# ethernet_chip.net
KiCad netlist of a schematic drawn in EAGLE
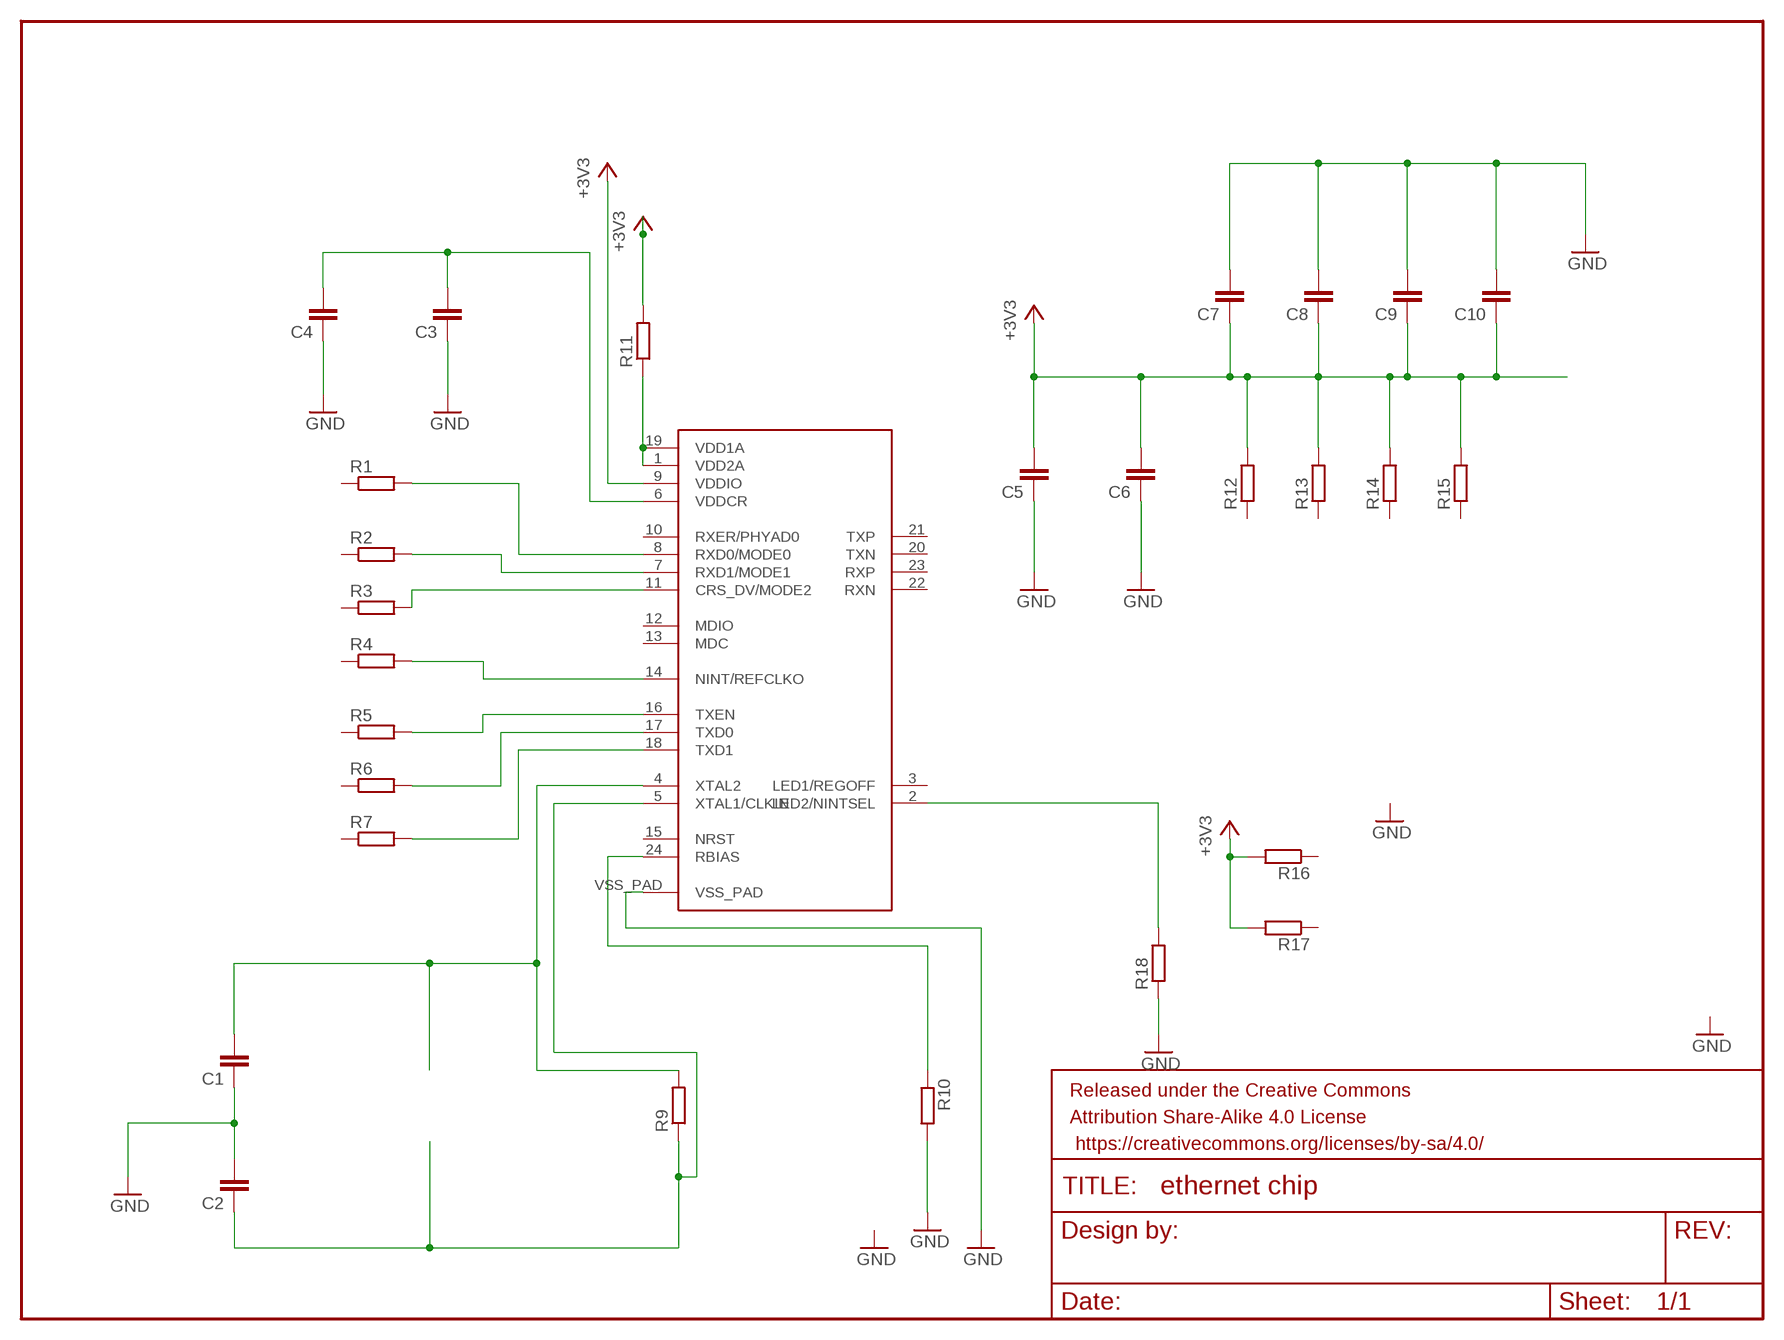
[diagram p0: schematic, sheet 1]

(export (version "E")
  (design (tool "Eeschema 10.0.6"))
  (components
    (comp (ref "C1")
      (value "CC0603")
      (footprint "eagle-import:C0603")
      (libsource (lib "eagle-import") (part "CC0603"))
    )
    (comp (ref "C2")
      (value "CC0603")
      (footprint "eagle-import:C0603")
      (libsource (lib "eagle-import") (part "CC0603"))
    )
    (comp (ref "C3")
      (value "CC0603")
      (footprint "eagle-import:C0603")
      (libsource (lib "eagle-import") (part "CC0603"))
    )
    (comp (ref "C4")
      (value "CC0603")
      (footprint "eagle-import:C0603")
      (libsource (lib "eagle-import") (part "CC0603"))
    )
    (comp (ref "C5")
      (value "CC0603")
      (footprint "eagle-import:C0603")
      (libsource (lib "eagle-import") (part "CC0603"))
    )
    (comp (ref "C6")
      (value "CC0603")
      (footprint "eagle-import:C0603")
      (libsource (lib "eagle-import") (part "CC0603"))
    )
    (comp (ref "C7")
      (value "CC0603")
      (footprint "eagle-import:C0603")
      (libsource (lib "eagle-import") (part "CC0603"))
    )
    (comp (ref "C8")
      (value "CC0603")
      (footprint "eagle-import:C0603")
      (libsource (lib "eagle-import") (part "CC0603"))
    )
    (comp (ref "C9")
      (value "CC0603")
      (footprint "eagle-import:C0603")
      (libsource (lib "eagle-import") (part "CC0603"))
    )
    (comp (ref "C10")
      (value "CC0603")
      (footprint "eagle-import:C0603")
      (libsource (lib "eagle-import") (part "CC0603"))
    )
    (comp (ref "FRAME1")
      (value "FRAME-LETTER")
      (footprint "eagle-import:CREATIVE_COMMONS")
      (libsource (lib "eagle-import") (part "FRAME-LETTER"))
    )
    (comp (ref "R1")
      (value "RR0603")
      (footprint "eagle-import:R0603")
      (libsource (lib "eagle-import") (part "RR0603"))
    )
    (comp (ref "R2")
      (value "RR0603")
      (footprint "eagle-import:R0603")
      (libsource (lib "eagle-import") (part "RR0603"))
    )
    (comp (ref "R3")
      (value "RR0603")
      (footprint "eagle-import:R0603")
      (libsource (lib "eagle-import") (part "RR0603"))
    )
    (comp (ref "R4")
      (value "RR0603")
      (footprint "eagle-import:R0603")
      (libsource (lib "eagle-import") (part "RR0603"))
    )
    (comp (ref "R5")
      (value "RR0603")
      (footprint "eagle-import:R0603")
      (libsource (lib "eagle-import") (part "RR0603"))
    )
    (comp (ref "R6")
      (value "RR0603")
      (footprint "eagle-import:R0603")
      (libsource (lib "eagle-import") (part "RR0603"))
    )
    (comp (ref "R7")
      (value "RR0603")
      (footprint "eagle-import:R0603")
      (libsource (lib "eagle-import") (part "RR0603"))
    )
    (comp (ref "R9")
      (value "RR0603")
      (footprint "eagle-import:R0603")
      (libsource (lib "eagle-import") (part "RR0603"))
    )
    (comp (ref "R10")
      (value "RR0603")
      (footprint "eagle-import:R0603")
      (libsource (lib "eagle-import") (part "RR0603"))
    )
    (comp (ref "R11")
      (value "RR0603")
      (footprint "eagle-import:R0603")
      (libsource (lib "eagle-import") (part "RR0603"))
    )
    (comp (ref "R12")
      (value "RR0603")
      (footprint "eagle-import:R0603")
      (libsource (lib "eagle-import") (part "RR0603"))
    )
    (comp (ref "R13")
      (value "RR0603")
      (footprint "eagle-import:R0603")
      (libsource (lib "eagle-import") (part "RR0603"))
    )
    (comp (ref "R14")
      (value "RR0603")
      (footprint "eagle-import:R0603")
      (libsource (lib "eagle-import") (part "RR0603"))
    )
    (comp (ref "R15")
      (value "RR0603")
      (footprint "eagle-import:R0603")
      (libsource (lib "eagle-import") (part "RR0603"))
    )
    (comp (ref "R16")
      (value "RR0603")
      (footprint "eagle-import:R0603")
      (libsource (lib "eagle-import") (part "RR0603"))
    )
    (comp (ref "R17")
      (value "RR0603")
      (footprint "eagle-import:R0603")
      (libsource (lib "eagle-import") (part "RR0603"))
    )
    (comp (ref "R18")
      (value "RR0603")
      (footprint "eagle-import:R0603")
      (libsource (lib "eagle-import") (part "RR0603"))
    )
    (comp (ref "U$1")
      (value "LAN8720LAN8720")
      (footprint "eagle-import:24-QFN")
      (libsource (lib "eagle-import") (part "LAN8720LAN8720"))
    )
  )
  (nets
    (net (code "1") (name "+3V3") (class "Default")
      (node (ref "C10") (pin "1") (pinfunction "1_1") (pintype "passive"))
      (node (ref "C5") (pin "2") (pinfunction "2_2") (pintype "passive"))
      (node (ref "C6") (pin "2") (pinfunction "2_2") (pintype "passive"))
      (node (ref "C7") (pin "1") (pinfunction "1_1") (pintype "passive"))
      (node (ref "C8") (pin "1") (pinfunction "1_1") (pintype "passive"))
      (node (ref "C9") (pin "1") (pinfunction "1_1") (pintype "passive"))
      (node (ref "R11") (pin "2") (pinfunction "2_2") (pintype "passive"))
      (node (ref "R12") (pin "2") (pinfunction "2_2") (pintype "passive"))
      (node (ref "R13") (pin "2") (pinfunction "2_2") (pintype "passive"))
      (node (ref "R14") (pin "2") (pinfunction "2_2") (pintype "passive"))
      (node (ref "R15") (pin "2") (pinfunction "2_2") (pintype "passive"))
      (node (ref "R16") (pin "2") (pinfunction "2_2") (pintype "passive"))
      (node (ref "R17") (pin "2") (pinfunction "2_2") (pintype "passive"))
      (node (ref "U$1") (pin "9") (pinfunction "VDDIO_9") (pintype "bidirectional"))
    )
    (net (code "2") (name "GND") (class "Default")
      (node (ref "C1") (pin "1") (pinfunction "1_1") (pintype "passive"))
      (node (ref "C10") (pin "2") (pinfunction "2_2") (pintype "passive"))
      (node (ref "C2") (pin "2") (pinfunction "2_2") (pintype "passive"))
      (node (ref "C3") (pin "1") (pinfunction "1_1") (pintype "passive"))
      (node (ref "C4") (pin "1") (pinfunction "1_1") (pintype "passive"))
      (node (ref "C5") (pin "1") (pinfunction "1_1") (pintype "passive"))
      (node (ref "C6") (pin "1") (pinfunction "1_1") (pintype "passive"))
      (node (ref "C7") (pin "2") (pinfunction "2_2") (pintype "passive"))
      (node (ref "C8") (pin "2") (pinfunction "2_2") (pintype "passive"))
      (node (ref "C9") (pin "2") (pinfunction "2_2") (pintype "passive"))
      (node (ref "R10") (pin "2") (pinfunction "2_2") (pintype "passive"))
      (node (ref "R18") (pin "1") (pinfunction "1_1") (pintype "passive"))
      (node (ref "U$1") (pin "VSS_PAD") (pinfunction "VSS_PAD_VSS_PAD") (pintype "bidirectional"))
    )
    (net (code "3") (name "Net-(U$1-CRS_DV{slash}MODE2)") (class "Default")
      (node (ref "R3") (pin "2") (pinfunction "2_2") (pintype "passive"))
      (node (ref "U$1") (pin "11") (pinfunction "CRS_DV/MODE2_11") (pintype "bidirectional"))
    )
    (net (code "4") (name "Net-(U$1-LED2{slash}NINTSEL)") (class "Default")
      (node (ref "R18") (pin "2") (pinfunction "2_2") (pintype "passive"))
      (node (ref "U$1") (pin "2") (pinfunction "LED2/NINTSEL_2") (pintype "bidirectional"))
    )
    (net (code "5") (name "Net-(U$1-NINT{slash}REFCLKO)") (class "Default")
      (node (ref "R4") (pin "2") (pinfunction "2_2") (pintype "passive"))
      (node (ref "U$1") (pin "14") (pinfunction "NINT/REFCLKO_14") (pintype "bidirectional"))
    )
    (net (code "6") (name "Net-(U$1-RBIAS)") (class "Default")
      (node (ref "R10") (pin "1") (pinfunction "1_1") (pintype "passive"))
      (node (ref "U$1") (pin "24") (pinfunction "RBIAS_24") (pintype "bidirectional"))
    )
    (net (code "7") (name "Net-(U$1-RXD0{slash}MODE0)") (class "Default")
      (node (ref "R1") (pin "2") (pinfunction "2_2") (pintype "passive"))
      (node (ref "U$1") (pin "8") (pinfunction "RXD0/MODE0_8") (pintype "bidirectional"))
    )
    (net (code "8") (name "Net-(U$1-RXD1{slash}MODE1)") (class "Default")
      (node (ref "R2") (pin "2") (pinfunction "2_2") (pintype "passive"))
      (node (ref "U$1") (pin "7") (pinfunction "RXD1/MODE1_7") (pintype "bidirectional"))
    )
    (net (code "9") (name "Net-(U$1-TXD0)") (class "Default")
      (node (ref "R6") (pin "2") (pinfunction "2_2") (pintype "passive"))
      (node (ref "U$1") (pin "17") (pinfunction "TXD0_17") (pintype "bidirectional"))
    )
    (net (code "10") (name "Net-(U$1-TXD1)") (class "Default")
      (node (ref "R7") (pin "2") (pinfunction "2_2") (pintype "passive"))
      (node (ref "U$1") (pin "18") (pinfunction "TXD1_18") (pintype "bidirectional"))
    )
    (net (code "11") (name "Net-(U$1-TXEN)") (class "Default")
      (node (ref "R5") (pin "2") (pinfunction "2_2") (pintype "passive"))
      (node (ref "U$1") (pin "16") (pinfunction "TXEN_16") (pintype "bidirectional"))
    )
    (net (code "12") (name "Net-(U$1-VDD1A)") (class "Default")
      (node (ref "R11") (pin "1") (pinfunction "1_1") (pintype "passive"))
      (node (ref "U$1") (pin "1") (pinfunction "VDD2A_1") (pintype "bidirectional"))
      (node (ref "U$1") (pin "19") (pinfunction "VDD1A_19") (pintype "bidirectional"))
    )
    (net (code "13") (name "Net-(U$1-VDDCR)") (class "Default")
      (node (ref "C3") (pin "2") (pinfunction "2_2") (pintype "passive"))
      (node (ref "C4") (pin "2") (pinfunction "2_2") (pintype "passive"))
      (node (ref "U$1") (pin "6") (pinfunction "VDDCR_6") (pintype "bidirectional"))
    )
    (net (code "14") (name "Net-(U$1-XTAL1{slash}CLKIN)") (class "Default")
      (node (ref "C2") (pin "1") (pinfunction "1_1") (pintype "passive"))
      (node (ref "R9") (pin "1") (pinfunction "1_1") (pintype "passive"))
      (node (ref "U$1") (pin "5") (pinfunction "XTAL1/CLKIN_5") (pintype "bidirectional"))
    )
    (net (code "15") (name "Net-(U$1-XTAL2)") (class "Default")
      (node (ref "C1") (pin "2") (pinfunction "2_2") (pintype "passive"))
      (node (ref "R9") (pin "2") (pinfunction "2_2") (pintype "passive"))
      (node (ref "U$1") (pin "4") (pinfunction "XTAL2_4") (pintype "bidirectional"))
    )
    (net (code "16") (name "unconnected-(R1-Pad1)") (class "Default")
      (node (ref "R1") (pin "1") (pinfunction "1_1") (pintype "passive"))
    )
    (net (code "17") (name "unconnected-(R2-Pad1)") (class "Default")
      (node (ref "R2") (pin "1") (pinfunction "1_1") (pintype "passive"))
    )
    (net (code "18") (name "unconnected-(R3-Pad1)") (class "Default")
      (node (ref "R3") (pin "1") (pinfunction "1_1") (pintype "passive"))
    )
    (net (code "19") (name "unconnected-(R4-Pad1)") (class "Default")
      (node (ref "R4") (pin "1") (pinfunction "1_1") (pintype "passive"))
    )
    (net (code "20") (name "unconnected-(R5-Pad1)") (class "Default")
      (node (ref "R5") (pin "1") (pinfunction "1_1") (pintype "passive"))
    )
    (net (code "21") (name "unconnected-(R6-Pad1)") (class "Default")
      (node (ref "R6") (pin "1") (pinfunction "1_1") (pintype "passive"))
    )
    (net (code "22") (name "unconnected-(R7-Pad1)") (class "Default")
      (node (ref "R7") (pin "1") (pinfunction "1_1") (pintype "passive"))
    )
    (net (code "23") (name "unconnected-(R12-Pad1)") (class "Default")
      (node (ref "R12") (pin "1") (pinfunction "1_1") (pintype "passive"))
    )
    (net (code "24") (name "unconnected-(R13-Pad1)") (class "Default")
      (node (ref "R13") (pin "1") (pinfunction "1_1") (pintype "passive"))
    )
    (net (code "25") (name "unconnected-(R14-Pad1)") (class "Default")
      (node (ref "R14") (pin "1") (pinfunction "1_1") (pintype "passive"))
    )
    (net (code "26") (name "unconnected-(R15-Pad1)") (class "Default")
      (node (ref "R15") (pin "1") (pinfunction "1_1") (pintype "passive"))
    )
    (net (code "27") (name "unconnected-(R16-Pad1)") (class "Default")
      (node (ref "R16") (pin "1") (pinfunction "1_1") (pintype "passive"))
    )
    (net (code "28") (name "unconnected-(R17-Pad1)") (class "Default")
      (node (ref "R17") (pin "1") (pinfunction "1_1") (pintype "passive"))
    )
    (net (code "29") (name "unconnected-(U$1-LED1{slash}REGOFF-Pad3)") (class "Default")
      (node (ref "U$1") (pin "3") (pinfunction "LED1/REGOFF_3") (pintype "bidirectional"))
    )
    (net (code "30") (name "unconnected-(U$1-MDC-Pad13)") (class "Default")
      (node (ref "U$1") (pin "13") (pinfunction "MDC_13") (pintype "bidirectional"))
    )
    (net (code "31") (name "unconnected-(U$1-MDIO-Pad12)") (class "Default")
      (node (ref "U$1") (pin "12") (pinfunction "MDIO_12") (pintype "bidirectional"))
    )
    (net (code "32") (name "unconnected-(U$1-NRST-Pad15)") (class "Default")
      (node (ref "U$1") (pin "15") (pinfunction "NRST_15") (pintype "bidirectional"))
    )
    (net (code "33") (name "unconnected-(U$1-RXER{slash}PHYAD0-Pad10)") (class "Default")
      (node (ref "U$1") (pin "10") (pinfunction "RXER/PHYAD0_10") (pintype "bidirectional"))
    )
    (net (code "34") (name "unconnected-(U$1-RXN-Pad22)") (class "Default")
      (node (ref "U$1") (pin "22") (pinfunction "RXN_22") (pintype "bidirectional"))
    )
    (net (code "35") (name "unconnected-(U$1-RXP-Pad23)") (class "Default")
      (node (ref "U$1") (pin "23") (pinfunction "RXP_23") (pintype "bidirectional"))
    )
    (net (code "36") (name "unconnected-(U$1-TXN-Pad20)") (class "Default")
      (node (ref "U$1") (pin "20") (pinfunction "TXN_20") (pintype "bidirectional"))
    )
    (net (code "37") (name "unconnected-(U$1-TXP-Pad21)") (class "Default")
      (node (ref "U$1") (pin "21") (pinfunction "TXP_21") (pintype "bidirectional"))
    )
  )
)
